# M_C_ext_main.net
KiCad netlist of a schematic drawn in EAGLE
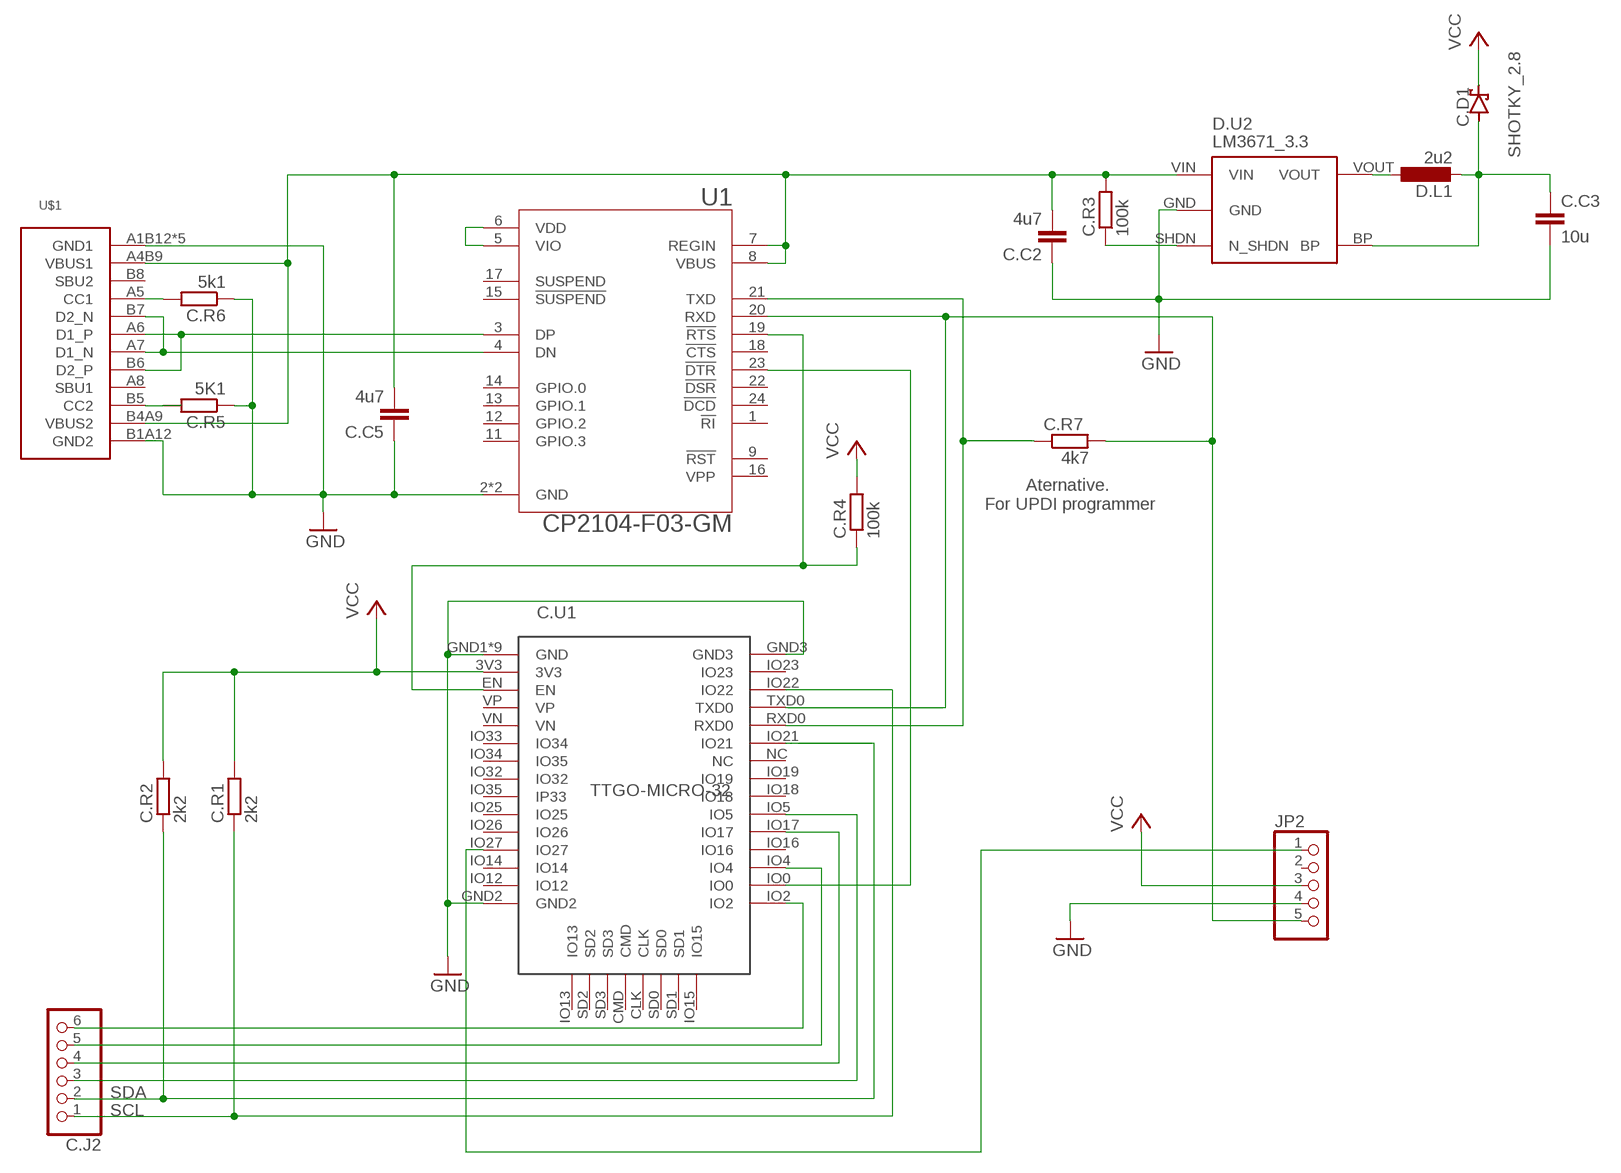
[diagram p0: schematic, sheet 1]

(export (version "E")
  (design (tool "Eeschema 10.0.6"))
  (components
    (comp (ref "C.C2")
      (value "4u7")
      (footprint "eagle-import:C0603")
      (libsource (lib "eagle-import") (part "C-EUC0603"))
    )
    (comp (ref "C.C3")
      (value "10u")
      (footprint "eagle-import:C0805")
      (libsource (lib "eagle-import") (part "C-EUC0805"))
    )
    (comp (ref "C.C5")
      (value "4u7")
      (footprint "eagle-import:C0603")
      (libsource (lib "eagle-import") (part "C-EUC0603"))
    )
    (comp (ref "C.D1")
      (value "SHOTKY_2.8")
      (footprint "eagle-import:SHOTKY_2.8")
      (libsource (lib "eagle-import") (part "SHOTKY_2.8"))
    )
    (comp (ref "C.J2")
      (value "PINHD-1X6")
      (footprint "eagle-import:1X06")
      (libsource (lib "eagle-import") (part "PINHD-1X6"))
    )
    (comp (ref "C.R1")
      (value "2k2")
      (footprint "eagle-import:R0603")
      (libsource (lib "eagle-import") (part "R-EU_R0603"))
    )
    (comp (ref "C.R2")
      (value "2k2")
      (footprint "eagle-import:R0603")
      (libsource (lib "eagle-import") (part "R-EU_R0603"))
    )
    (comp (ref "C.R3")
      (value "100k")
      (footprint "eagle-import:R0603")
      (libsource (lib "eagle-import") (part "R-EU_R0603"))
    )
    (comp (ref "C.R4")
      (value "100k")
      (footprint "eagle-import:R0603")
      (libsource (lib "eagle-import") (part "R-EU_R0603"))
    )
    (comp (ref "C.R5")
      (value "5K1")
      (footprint "eagle-import:R0603")
      (libsource (lib "eagle-import") (part "R-EU_R0603"))
    )
    (comp (ref "C.R6")
      (value "5k1")
      (footprint "eagle-import:R0603")
      (libsource (lib "eagle-import") (part "R-EU_R0603"))
    )
    (comp (ref "C.R7")
      (value "4k7")
      (footprint "eagle-import:R0603")
      (libsource (lib "eagle-import") (part "R-EU_R0603"))
    )
    (comp (ref "C.U1")
      (value "TTGO-MICRO-32")
      (footprint "eagle-import:TTGO-MICRO-32")
      (libsource (lib "eagle-import") (part "TTGO-MICRO-32"))
    )
    (comp (ref "D.L1")
      (value "2u2")
      (footprint "eagle-import:L3230M")
      (libsource (lib "eagle-import") (part "L-EUL3230M"))
    )
    (comp (ref "D.U2")
      (value "LM3671_3.3")
      (footprint "eagle-import:SOT32-5")
      (libsource (lib "eagle-import") (part "STABILISER_APE8865"))
    )
    (comp (ref "JP2")
      (value "PINHD-1X5")
      (footprint "eagle-import:1X05")
      (libsource (lib "eagle-import") (part "PINHD-1X5"))
    )
    (comp (ref "U$1")
      (value "USB-C")
      (footprint "eagle-import:USB-C")
      (libsource (lib "eagle-import") (part "USB-C"))
    )
    (comp (ref "U1")
      (value "CP2104-F03-GM")
      (footprint "eagle-import:QFN50P400X400X80-25N")
      (fields (field (name "MF") "Silicon Labs") (field (name "MP") "CP2104"))
      (libsource (lib "eagle-import") (part "CP2104-F03-GM"))
    )
  )
  (nets
    (net (code "1") (name "/SCL") (class "Default")
      (node (ref "C.J2") (pin "1") (pinfunction "1_1") (pintype "passive"))
      (node (ref "C.R1") (pin "1") (pinfunction "1_1") (pintype "passive"))
      (node (ref "C.U1") (pin "IO22") (pinfunction "IO22_IO22") (pintype "bidirectional"))
    )
    (net (code "2") (name "/SDA") (class "Default")
      (node (ref "C.J2") (pin "2") (pinfunction "2_2") (pintype "passive"))
      (node (ref "C.R2") (pin "1") (pinfunction "1_1") (pintype "passive"))
      (node (ref "C.U1") (pin "IO21") (pinfunction "IO21_IO21") (pintype "bidirectional"))
    )
    (net (code "3") (name "GND") (class "Default")
      (node (ref "C.C2") (pin "1") (pinfunction "1_1") (pintype "passive"))
      (node (ref "C.C3") (pin "2") (pinfunction "2_2") (pintype "passive"))
      (node (ref "C.C5") (pin "1") (pinfunction "1_1") (pintype "passive"))
      (node (ref "C.R5") (pin "1") (pinfunction "1_1") (pintype "passive"))
      (node (ref "C.R6") (pin "1") (pinfunction "1_1") (pintype "passive"))
      (node (ref "C.U1") (pin "GND1") (pinfunction "GND_GND1") (pintype "power_in"))
      (node (ref "C.U1") (pin "GND10") (pinfunction "GND_GND10") (pintype "power_in"))
      (node (ref "C.U1") (pin "GND11") (pinfunction "GND_GND11") (pintype "power_in"))
      (node (ref "C.U1") (pin "GND2") (pinfunction "GND2_GND2") (pintype "power_in"))
      (node (ref "C.U1") (pin "GND3") (pinfunction "GND3_GND3") (pintype "power_in"))
      (node (ref "C.U1") (pin "GND4") (pinfunction "GND_GND4") (pintype "power_in"))
      (node (ref "C.U1") (pin "GND5") (pinfunction "GND_GND5") (pintype "power_in"))
      (node (ref "C.U1") (pin "GND6") (pinfunction "GND_GND6") (pintype "power_in"))
      (node (ref "C.U1") (pin "GND7") (pinfunction "GND_GND7") (pintype "power_in"))
      (node (ref "C.U1") (pin "GND8") (pinfunction "GND_GND8") (pintype "power_in"))
      (node (ref "C.U1") (pin "GND9") (pinfunction "GND_GND9") (pintype "power_in"))
      (node (ref "D.U2") (pin "GND") (pinfunction "GND_GND") (pintype "bidirectional"))
      (node (ref "JP2") (pin "4") (pinfunction "4_4") (pintype "passive"))
      (node (ref "U$1") (pin "A1B12") (pinfunction "GND1_A1B12") (pintype "bidirectional"))
      (node (ref "U$1") (pin "B1A12") (pinfunction "GND2_B1A12") (pintype "bidirectional"))
      (node (ref "U$1") (pin "SH1") (pinfunction "GND1_SH1") (pintype "bidirectional"))
      (node (ref "U$1") (pin "SH2") (pinfunction "GND1_SH2") (pintype "bidirectional"))
      (node (ref "U$1") (pin "SH3") (pinfunction "GND1_SH3") (pintype "bidirectional"))
      (node (ref "U$1") (pin "SH4") (pinfunction "GND1_SH4") (pintype "bidirectional"))
      (node (ref "U1") (pin "2") (pinfunction "GND_2") (pintype "power_in"))
      (node (ref "U1") (pin "25") (pinfunction "GND_25") (pintype "power_in"))
    )
    (net (code "4") (name "Net-(C.C3-Pad1)") (class "Default")
      (node (ref "C.C3") (pin "1") (pinfunction "1_1") (pintype "passive"))
      (node (ref "C.D1") (pin "A") (pinfunction "A_A") (pintype "passive"))
      (node (ref "D.L1") (pin "2") (pinfunction "2_2") (pintype "passive"))
      (node (ref "D.U2") (pin "BP") (pinfunction "BP_BP") (pintype "bidirectional"))
    )
    (net (code "5") (name "Net-(C.J2-Pad3)") (class "Default")
      (node (ref "C.J2") (pin "3") (pinfunction "3_3") (pintype "passive"))
      (node (ref "C.U1") (pin "IO5") (pinfunction "IO5_IO5") (pintype "bidirectional"))
    )
    (net (code "6") (name "Net-(C.J2-Pad4)") (class "Default")
      (node (ref "C.J2") (pin "4") (pinfunction "4_4") (pintype "passive"))
      (node (ref "C.U1") (pin "IO17") (pinfunction "IO17_IO17") (pintype "bidirectional"))
    )
    (net (code "7") (name "Net-(C.J2-Pad5)") (class "Default")
      (node (ref "C.J2") (pin "5") (pinfunction "5_5") (pintype "passive"))
      (node (ref "C.U1") (pin "IO4") (pinfunction "IO4_IO4") (pintype "bidirectional"))
    )
    (net (code "8") (name "Net-(C.J2-Pad6)") (class "Default")
      (node (ref "C.J2") (pin "6") (pinfunction "6_6") (pintype "passive"))
      (node (ref "C.U1") (pin "IO2") (pinfunction "IO2_IO2") (pintype "bidirectional"))
    )
    (net (code "9") (name "Net-(C.U1-PadIO27)") (class "Default")
      (node (ref "C.U1") (pin "IO27") (pinfunction "IO27_IO27") (pintype "bidirectional"))
      (node (ref "JP2") (pin "1") (pinfunction "1_1") (pintype "passive"))
    )
    (net (code "10") (name "Net-(D.L1-Pad1)") (class "Default")
      (node (ref "D.L1") (pin "1") (pinfunction "1_1") (pintype "passive"))
      (node (ref "D.U2") (pin "VOUT") (pinfunction "VOUT_VOUT") (pintype "bidirectional"))
    )
    (net (code "11") (name "Net-(D.U2-N_SHDN)") (class "Default")
      (node (ref "C.R3") (pin "1") (pinfunction "1_1") (pintype "passive"))
      (node (ref "D.U2") (pin "SHDN") (pinfunction "N_SHDN_SHDN") (pintype "bidirectional"))
    )
    (net (code "12") (name "Net-(U$1-CC1)") (class "Default")
      (node (ref "C.R6") (pin "2") (pinfunction "2_2") (pintype "passive"))
      (node (ref "U$1") (pin "A5") (pinfunction "CC1_A5") (pintype "bidirectional"))
    )
    (net (code "13") (name "Net-(U$1-CC2)") (class "Default")
      (node (ref "C.R5") (pin "2") (pinfunction "2_2") (pintype "passive"))
      (node (ref "U$1") (pin "B5") (pinfunction "CC2_B5") (pintype "bidirectional"))
    )
    (net (code "14") (name "Net-(U$1-D1_N)") (class "Default")
      (node (ref "U$1") (pin "A7") (pinfunction "D1_N_A7") (pintype "bidirectional"))
      (node (ref "U$1") (pin "B7") (pinfunction "D2_N_B7") (pintype "bidirectional"))
      (node (ref "U1") (pin "4") (pinfunction "DN_4") (pintype "bidirectional"))
    )
    (net (code "15") (name "Net-(U$1-D1_P)") (class "Default")
      (node (ref "U$1") (pin "A6") (pinfunction "D1_P_A6") (pintype "bidirectional"))
      (node (ref "U$1") (pin "B6") (pinfunction "D2_P_B6") (pintype "bidirectional"))
      (node (ref "U1") (pin "3") (pinfunction "DP_3") (pintype "bidirectional"))
    )
    (net (code "16") (name "Net-(U$1-VBUS1)") (class "Default")
      (node (ref "C.C2") (pin "2") (pinfunction "2_2") (pintype "passive"))
      (node (ref "C.C5") (pin "2") (pinfunction "2_2") (pintype "passive"))
      (node (ref "C.R3") (pin "2") (pinfunction "2_2") (pintype "passive"))
      (node (ref "D.U2") (pin "VIN") (pinfunction "VIN_VIN") (pintype "bidirectional"))
      (node (ref "U$1") (pin "A4B9") (pinfunction "VBUS1_A4B9") (pintype "bidirectional"))
      (node (ref "U$1") (pin "B4A9") (pinfunction "VBUS2_B4A9") (pintype "bidirectional"))
      (node (ref "U1") (pin "7") (pinfunction "REGIN_7") (pintype "input"))
      (node (ref "U1") (pin "8") (pinfunction "VBUS_8") (pintype "input"))
    )
    (net (code "17") (name "Net-(U1-RXD)") (class "Default")
      (node (ref "C.R7") (pin "2") (pinfunction "2_2") (pintype "passive"))
      (node (ref "C.U1") (pin "TXD0") (pinfunction "TXD0_TXD0") (pintype "bidirectional"))
      (node (ref "JP2") (pin "5") (pinfunction "5_5") (pintype "passive"))
      (node (ref "U1") (pin "20") (pinfunction "RXD_20") (pintype "input"))
    )
    (net (code "18") (name "Net-(U1-TXD)") (class "Default")
      (node (ref "C.R7") (pin "1") (pinfunction "1_1") (pintype "passive"))
      (node (ref "C.U1") (pin "RXD0") (pinfunction "RXD0_RXD0") (pintype "bidirectional"))
      (node (ref "U1") (pin "21") (pinfunction "TXD_21") (pintype "output"))
    )
    (net (code "19") (name "Net-(U1-VDD)") (class "Default")
      (node (ref "U1") (pin "5") (pinfunction "VIO_5") (pintype "power_in"))
      (node (ref "U1") (pin "6") (pinfunction "VDD_6") (pintype "power_in"))
    )
    (net (code "20") (name "Net-(U1-~{DTR})") (class "Default")
      (node (ref "C.U1") (pin "IO0") (pinfunction "IO0_IO0") (pintype "bidirectional"))
      (node (ref "U1") (pin "23") (pinfunction "~{DTR}_23") (pintype "output"))
    )
    (net (code "21") (name "Net-(U1-~{RTS})") (class "Default")
      (node (ref "C.R4") (pin "1") (pinfunction "1_1") (pintype "passive"))
      (node (ref "C.U1") (pin "EN") (pinfunction "EN_EN") (pintype "bidirectional"))
      (node (ref "U1") (pin "19") (pinfunction "~{RTS}_19") (pintype "output"))
    )
    (net (code "22") (name "VCC") (class "Default")
      (node (ref "C.D1") (pin "K") (pinfunction "C_K") (pintype "passive"))
      (node (ref "C.R1") (pin "2") (pinfunction "2_2") (pintype "passive"))
      (node (ref "C.R2") (pin "2") (pinfunction "2_2") (pintype "passive"))
      (node (ref "C.R4") (pin "2") (pinfunction "2_2") (pintype "passive"))
      (node (ref "C.U1") (pin "3V3") (pinfunction "3V3_3V3") (pintype "power_in"))
      (node (ref "JP2") (pin "3") (pinfunction "3_3") (pintype "passive"))
    )
    (net (code "23") (name "unconnected-(C.U1-IO34-PadIO33)") (class "Default")
      (node (ref "C.U1") (pin "IO33") (pinfunction "IO34_IO33") (pintype "bidirectional"))
    )
    (net (code "24") (name "unconnected-(C.U1-IO35-PadIO34)") (class "Default")
      (node (ref "C.U1") (pin "IO34") (pinfunction "IO35_IO34") (pintype "bidirectional"))
    )
    (net (code "25") (name "unconnected-(C.U1-IP33-PadIO35)") (class "Default")
      (node (ref "C.U1") (pin "IO35") (pinfunction "IP33_IO35") (pintype "bidirectional"))
    )
    (net (code "26") (name "unconnected-(C.U1-PadCLK)") (class "Default")
      (node (ref "C.U1") (pin "CLK") (pinfunction "CLK_CLK") (pintype "bidirectional"))
    )
    (net (code "27") (name "unconnected-(C.U1-PadCMD)") (class "Default")
      (node (ref "C.U1") (pin "CMD") (pinfunction "CMD_CMD") (pintype "bidirectional"))
    )
    (net (code "28") (name "unconnected-(C.U1-PadIO12)") (class "Default")
      (node (ref "C.U1") (pin "IO12") (pinfunction "IO12_IO12") (pintype "bidirectional"))
    )
    (net (code "29") (name "unconnected-(C.U1-PadIO13)") (class "Default")
      (node (ref "C.U1") (pin "IO13") (pinfunction "IO13_IO13") (pintype "bidirectional"))
    )
    (net (code "30") (name "unconnected-(C.U1-PadIO14)") (class "Default")
      (node (ref "C.U1") (pin "IO14") (pinfunction "IO14_IO14") (pintype "bidirectional"))
    )
    (net (code "31") (name "unconnected-(C.U1-PadIO15)") (class "Default")
      (node (ref "C.U1") (pin "IO15") (pinfunction "IO15_IO15") (pintype "bidirectional"))
    )
    (net (code "32") (name "unconnected-(C.U1-PadIO16)") (class "Default")
      (node (ref "C.U1") (pin "IO16") (pinfunction "IO16_IO16") (pintype "bidirectional"))
    )
    (net (code "33") (name "unconnected-(C.U1-PadIO18)") (class "Default")
      (node (ref "C.U1") (pin "IO18") (pinfunction "IO18_IO18") (pintype "bidirectional"))
    )
    (net (code "34") (name "unconnected-(C.U1-PadIO19)") (class "Default")
      (node (ref "C.U1") (pin "IO19") (pinfunction "IO19_IO19") (pintype "bidirectional"))
    )
    (net (code "35") (name "unconnected-(C.U1-PadIO23)") (class "Default")
      (node (ref "C.U1") (pin "IO23") (pinfunction "IO23_IO23") (pintype "bidirectional"))
    )
    (net (code "36") (name "unconnected-(C.U1-PadIO25)") (class "Default")
      (node (ref "C.U1") (pin "IO25") (pinfunction "IO25_IO25") (pintype "bidirectional"))
    )
    (net (code "37") (name "unconnected-(C.U1-PadIO26)") (class "Default")
      (node (ref "C.U1") (pin "IO26") (pinfunction "IO26_IO26") (pintype "bidirectional"))
    )
    (net (code "38") (name "unconnected-(C.U1-PadIO32)") (class "Default")
      (node (ref "C.U1") (pin "IO32") (pinfunction "IO32_IO32") (pintype "bidirectional"))
    )
    (net (code "39") (name "unconnected-(C.U1-PadNC)") (class "Default")
      (node (ref "C.U1") (pin "NC") (pinfunction "NC_NC") (pintype "no_connect"))
    )
    (net (code "40") (name "unconnected-(C.U1-PadSD0)") (class "Default")
      (node (ref "C.U1") (pin "SD0") (pinfunction "SD0_SD0") (pintype "bidirectional"))
    )
    (net (code "41") (name "unconnected-(C.U1-PadSD1)") (class "Default")
      (node (ref "C.U1") (pin "SD1") (pinfunction "SD1_SD1") (pintype "bidirectional"))
    )
    (net (code "42") (name "unconnected-(C.U1-PadSD2)") (class "Default")
      (node (ref "C.U1") (pin "SD2") (pinfunction "SD2_SD2") (pintype "bidirectional"))
    )
    (net (code "43") (name "unconnected-(C.U1-PadSD3)") (class "Default")
      (node (ref "C.U1") (pin "SD3") (pinfunction "SD3_SD3") (pintype "bidirectional"))
    )
    (net (code "44") (name "unconnected-(C.U1-PadVN)") (class "Default")
      (node (ref "C.U1") (pin "VN") (pinfunction "VN_VN") (pintype "bidirectional"))
    )
    (net (code "45") (name "unconnected-(C.U1-PadVP)") (class "Default")
      (node (ref "C.U1") (pin "VP") (pinfunction "VP_VP") (pintype "bidirectional"))
    )
    (net (code "46") (name "unconnected-(JP2-Pad2)") (class "Default")
      (node (ref "JP2") (pin "2") (pinfunction "2_2") (pintype "passive"))
    )
    (net (code "47") (name "unconnected-(U$1-SBU1-PadA8)") (class "Default")
      (node (ref "U$1") (pin "A8") (pinfunction "SBU1_A8") (pintype "bidirectional"))
    )
    (net (code "48") (name "unconnected-(U$1-SBU2-PadB8)") (class "Default")
      (node (ref "U$1") (pin "B8") (pinfunction "SBU2_B8") (pintype "bidirectional"))
    )
    (net (code "49") (name "unconnected-(U1-GPIO.0-Pad14)") (class "Default")
      (node (ref "U1") (pin "14") (pinfunction "GPIO.0_14") (pintype "bidirectional"))
    )
    (net (code "50") (name "unconnected-(U1-GPIO.1-Pad13)") (class "Default")
      (node (ref "U1") (pin "13") (pinfunction "GPIO.1_13") (pintype "bidirectional"))
    )
    (net (code "51") (name "unconnected-(U1-GPIO.2-Pad12)") (class "Default")
      (node (ref "U1") (pin "12") (pinfunction "GPIO.2_12") (pintype "bidirectional"))
    )
    (net (code "52") (name "unconnected-(U1-GPIO.3-Pad11)") (class "Default")
      (node (ref "U1") (pin "11") (pinfunction "GPIO.3_11") (pintype "bidirectional"))
    )
    (net (code "53") (name "unconnected-(U1-SUSPEND-Pad17)") (class "Default")
      (node (ref "U1") (pin "17") (pinfunction "SUSPEND_17") (pintype "output"))
    )
    (net (code "54") (name "unconnected-(U1-VPP-Pad16)") (class "Default")
      (node (ref "U1") (pin "16") (pinfunction "VPP_16") (pintype "passive"))
    )
    (net (code "55") (name "unconnected-(U1-~{CTS}-Pad18)") (class "Default")
      (node (ref "U1") (pin "18") (pinfunction "~{CTS}_18") (pintype "input"))
    )
    (net (code "56") (name "unconnected-(U1-~{DCD}-Pad24)") (class "Default")
      (node (ref "U1") (pin "24") (pinfunction "~{DCD}_24") (pintype "input"))
    )
    (net (code "57") (name "unconnected-(U1-~{DSR}-Pad22)") (class "Default")
      (node (ref "U1") (pin "22") (pinfunction "~{DSR}_22") (pintype "input"))
    )
    (net (code "58") (name "unconnected-(U1-~{RI}-Pad1)") (class "Default")
      (node (ref "U1") (pin "1") (pinfunction "~{RI}_1") (pintype "input"))
    )
    (net (code "59") (name "unconnected-(U1-~{RST}-Pad9)") (class "Default")
      (node (ref "U1") (pin "9") (pinfunction "~{RST}_9") (pintype "bidirectional"))
    )
    (net (code "60") (name "unconnected-(U1-~{SUSPEND}-Pad15)") (class "Default")
      (node (ref "U1") (pin "15") (pinfunction "~{SUSPEND}_15") (pintype "output"))
    )
  )
)
